# 04_Pin_Headers.net
KiCad netlist of a schematic drawn in Altium Designer
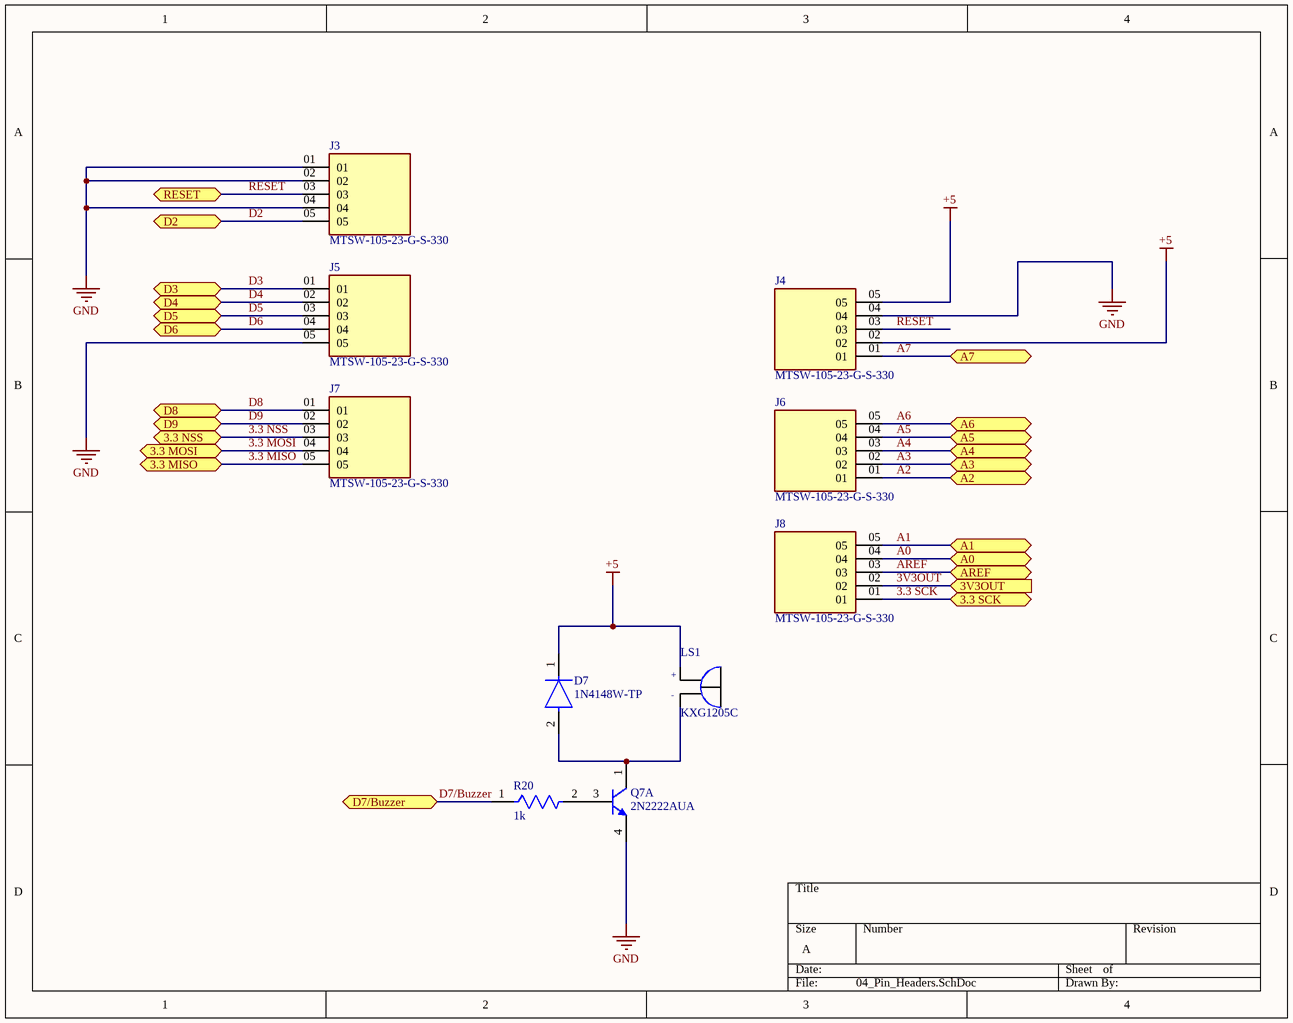
[diagram p0: 04_Pin_Headers.SchDoc]

(export (version "E")
  (design (tool "Eeschema 10.0.6"))
  (components
    (comp (ref "D7")
      (value "1N4148W-TP")
      (footprint "FP-SOD-123-IPC_A")
      (description "DIODE GEN PURP 100V 150MA SOD123")
      (libsource (lib "Altium Content Vault") (part "d7152d700b627762746794eb795d46e"))
    )
    (comp (ref "J3")
      (value "MTSW-105-23-G-S-330")
      (footprint "SAMTEC_MTSW-105-23-G-S-330")
      (libsource (lib "MTSW-105-23-G-S-330") (part "MTSW-105-23-G-S-330"))
    )
    (comp (ref "J4")
      (value "MTSW-105-23-G-S-330")
      (footprint "SAMTEC_MTSW-105-23-G-S-330")
      (libsource (lib "") (part "MTSW-105-23-G-S-330_1"))
    )
    (comp (ref "J5")
      (value "MTSW-105-23-G-S-330")
      (footprint "SAMTEC_MTSW-105-23-G-S-330")
      (libsource (lib "MTSW-105-23-G-S-330") (part "MTSW-105-23-G-S-330"))
    )
    (comp (ref "J6")
      (value "MTSW-105-23-G-S-330")
      (footprint "SAMTEC_MTSW-105-23-G-S-330")
      (libsource (lib "") (part "MTSW-105-23-G-S-330_1"))
    )
    (comp (ref "J7")
      (value "MTSW-105-23-G-S-330")
      (footprint "SAMTEC_MTSW-105-23-G-S-330")
      (libsource (lib "MTSW-105-23-G-S-330") (part "MTSW-105-23-G-S-330"))
    )
    (comp (ref "J8")
      (value "MTSW-105-23-G-S-330")
      (footprint "SAMTEC_MTSW-105-23-G-S-330")
      (libsource (lib "") (part "MTSW-105-23-G-S-330_1"))
    )
    (comp (ref "LS1")
      (value "KXG1205C")
      (footprint "*XDCR_KXG1205C_KXG1205C(Primary)")
      (libsource (lib "KXG1205C") (part "KXG1205C"))
    )
    (comp (ref "Q7")
      (value "2N2222AUA")
      (footprint "TT-MO-041BA-3_L")
      (description "Silicon Switching NPN Transistor, 800 mA, 50 V, -65 to 200 degC, 4-Pin LCC (MO-041BA), RoHS")
      (fields (field (name "MANUFACTURER") "TT Electronics"))
      (libsource (lib "Altium Content Vault") (part "BJT-NPN-CNBE-4"))
    )
    (comp (ref "R20")
      (value "1k")
      (footprint "FP-TNPW1206-e3-MFG")
      (description "TNPW12061K00BEEA")
      (fields (field (name "TOLERANCE") "0.1%"))
      (libsource (lib "Altium Content Vault") (part "1029c3af85768c4190bb7ad29bc67b5"))
    )
  )
  (nets
    (net (code "1") (name "+5") (class "Default")
      (node (ref "D7") (pin "1") (pinfunction "C_1") (pintype "passive"))
      (node (ref "J4") (pin "02") (pinfunction "02_02") (pintype "passive"))
      (node (ref "J4") (pin "05") (pinfunction "05_05") (pintype "passive"))
      (node (ref "LS1") (pin "P") (pinfunction "POS_P") (pintype "passive"))
    )
    (net (code "2") (name "/3.3 MISO") (class "Default")
      (node (ref "J7") (pin "05") (pinfunction "05_05") (pintype "passive"))
    )
    (net (code "3") (name "/3.3 MOSI") (class "Default")
      (node (ref "J7") (pin "04") (pinfunction "04_04") (pintype "passive"))
    )
    (net (code "4") (name "/3.3 NSS") (class "Default")
      (node (ref "J7") (pin "03") (pinfunction "03_03") (pintype "passive"))
    )
    (net (code "5") (name "/3.3 SCK") (class "Default")
      (node (ref "J8") (pin "01") (pinfunction "01_01") (pintype "passive"))
    )
    (net (code "6") (name "/3V3OUT") (class "Default")
      (node (ref "J8") (pin "02") (pinfunction "02_02") (pintype "passive"))
    )
    (net (code "7") (name "/A0") (class "Default")
      (node (ref "J8") (pin "04") (pinfunction "04_04") (pintype "passive"))
    )
    (net (code "8") (name "/A1") (class "Default")
      (node (ref "J8") (pin "05") (pinfunction "05_05") (pintype "passive"))
    )
    (net (code "9") (name "/A2") (class "Default")
      (node (ref "J6") (pin "01") (pinfunction "01_01") (pintype "passive"))
    )
    (net (code "10") (name "/A3") (class "Default")
      (node (ref "J6") (pin "02") (pinfunction "02_02") (pintype "passive"))
    )
    (net (code "11") (name "/A4") (class "Default")
      (node (ref "J6") (pin "03") (pinfunction "03_03") (pintype "passive"))
    )
    (net (code "12") (name "/A5") (class "Default")
      (node (ref "J6") (pin "04") (pinfunction "04_04") (pintype "passive"))
    )
    (net (code "13") (name "/A6") (class "Default")
      (node (ref "J6") (pin "05") (pinfunction "05_05") (pintype "passive"))
    )
    (net (code "14") (name "/A7") (class "Default")
      (node (ref "J4") (pin "01") (pinfunction "01_01") (pintype "passive"))
    )
    (net (code "15") (name "/AREF") (class "Default")
      (node (ref "J8") (pin "03") (pinfunction "03_03") (pintype "passive"))
    )
    (net (code "16") (name "/D2") (class "Default")
      (node (ref "J3") (pin "05") (pinfunction "05_05") (pintype "passive"))
    )
    (net (code "17") (name "/D3") (class "Default")
      (node (ref "J5") (pin "01") (pinfunction "01_01") (pintype "passive"))
    )
    (net (code "18") (name "/D4") (class "Default")
      (node (ref "J5") (pin "02") (pinfunction "02_02") (pintype "passive"))
    )
    (net (code "19") (name "/D5") (class "Default")
      (node (ref "J5") (pin "03") (pinfunction "03_03") (pintype "passive"))
    )
    (net (code "20") (name "/D6") (class "Default")
      (node (ref "J5") (pin "04") (pinfunction "04_04") (pintype "passive"))
    )
    (net (code "21") (name "/D7{slash}Buzzer") (class "Default")
      (node (ref "R20") (pin "1") (pinfunction "1_1") (pintype "passive"))
    )
    (net (code "22") (name "/D8") (class "Default")
      (node (ref "J7") (pin "01") (pinfunction "01_01") (pintype "passive"))
    )
    (net (code "23") (name "/D9") (class "Default")
      (node (ref "J7") (pin "02") (pinfunction "02_02") (pintype "passive"))
    )
    (net (code "24") (name "/RESET") (class "Default")
      (node (ref "J3") (pin "03") (pinfunction "03_03") (pintype "passive"))
      (node (ref "J4") (pin "03") (pinfunction "03_03") (pintype "passive"))
    )
    (net (code "25") (name "GND") (class "Default")
      (node (ref "J3") (pin "01") (pinfunction "01_01") (pintype "passive"))
      (node (ref "J3") (pin "02") (pinfunction "02_02") (pintype "passive"))
      (node (ref "J3") (pin "04") (pinfunction "04_04") (pintype "passive"))
      (node (ref "J4") (pin "04") (pinfunction "04_04") (pintype "passive"))
      (node (ref "J5") (pin "05") (pinfunction "05_05") (pintype "passive"))
      (node (ref "Q7") (pin "4") (pinfunction "E_4") (pintype "passive"))
    )
    (net (code "26") (name "Net-(D7-A)") (class "Default")
      (node (ref "D7") (pin "2") (pinfunction "A_2") (pintype "passive"))
      (node (ref "LS1") (pin "N") (pinfunction "NEG_N") (pintype "passive"))
      (node (ref "Q7") (pin "1") (pinfunction "C_1") (pintype "passive"))
    )
    (net (code "27") (name "Net-(Q7A-B)") (class "Default")
      (node (ref "Q7") (pin "3") (pinfunction "B_3") (pintype "passive"))
      (node (ref "R20") (pin "2") (pinfunction "2_2") (pintype "passive"))
    )
  )
)
